# AT42QT1010_Capacitive_Touch_Breakout.net
KiCad netlist of a schematic drawn in EAGLE
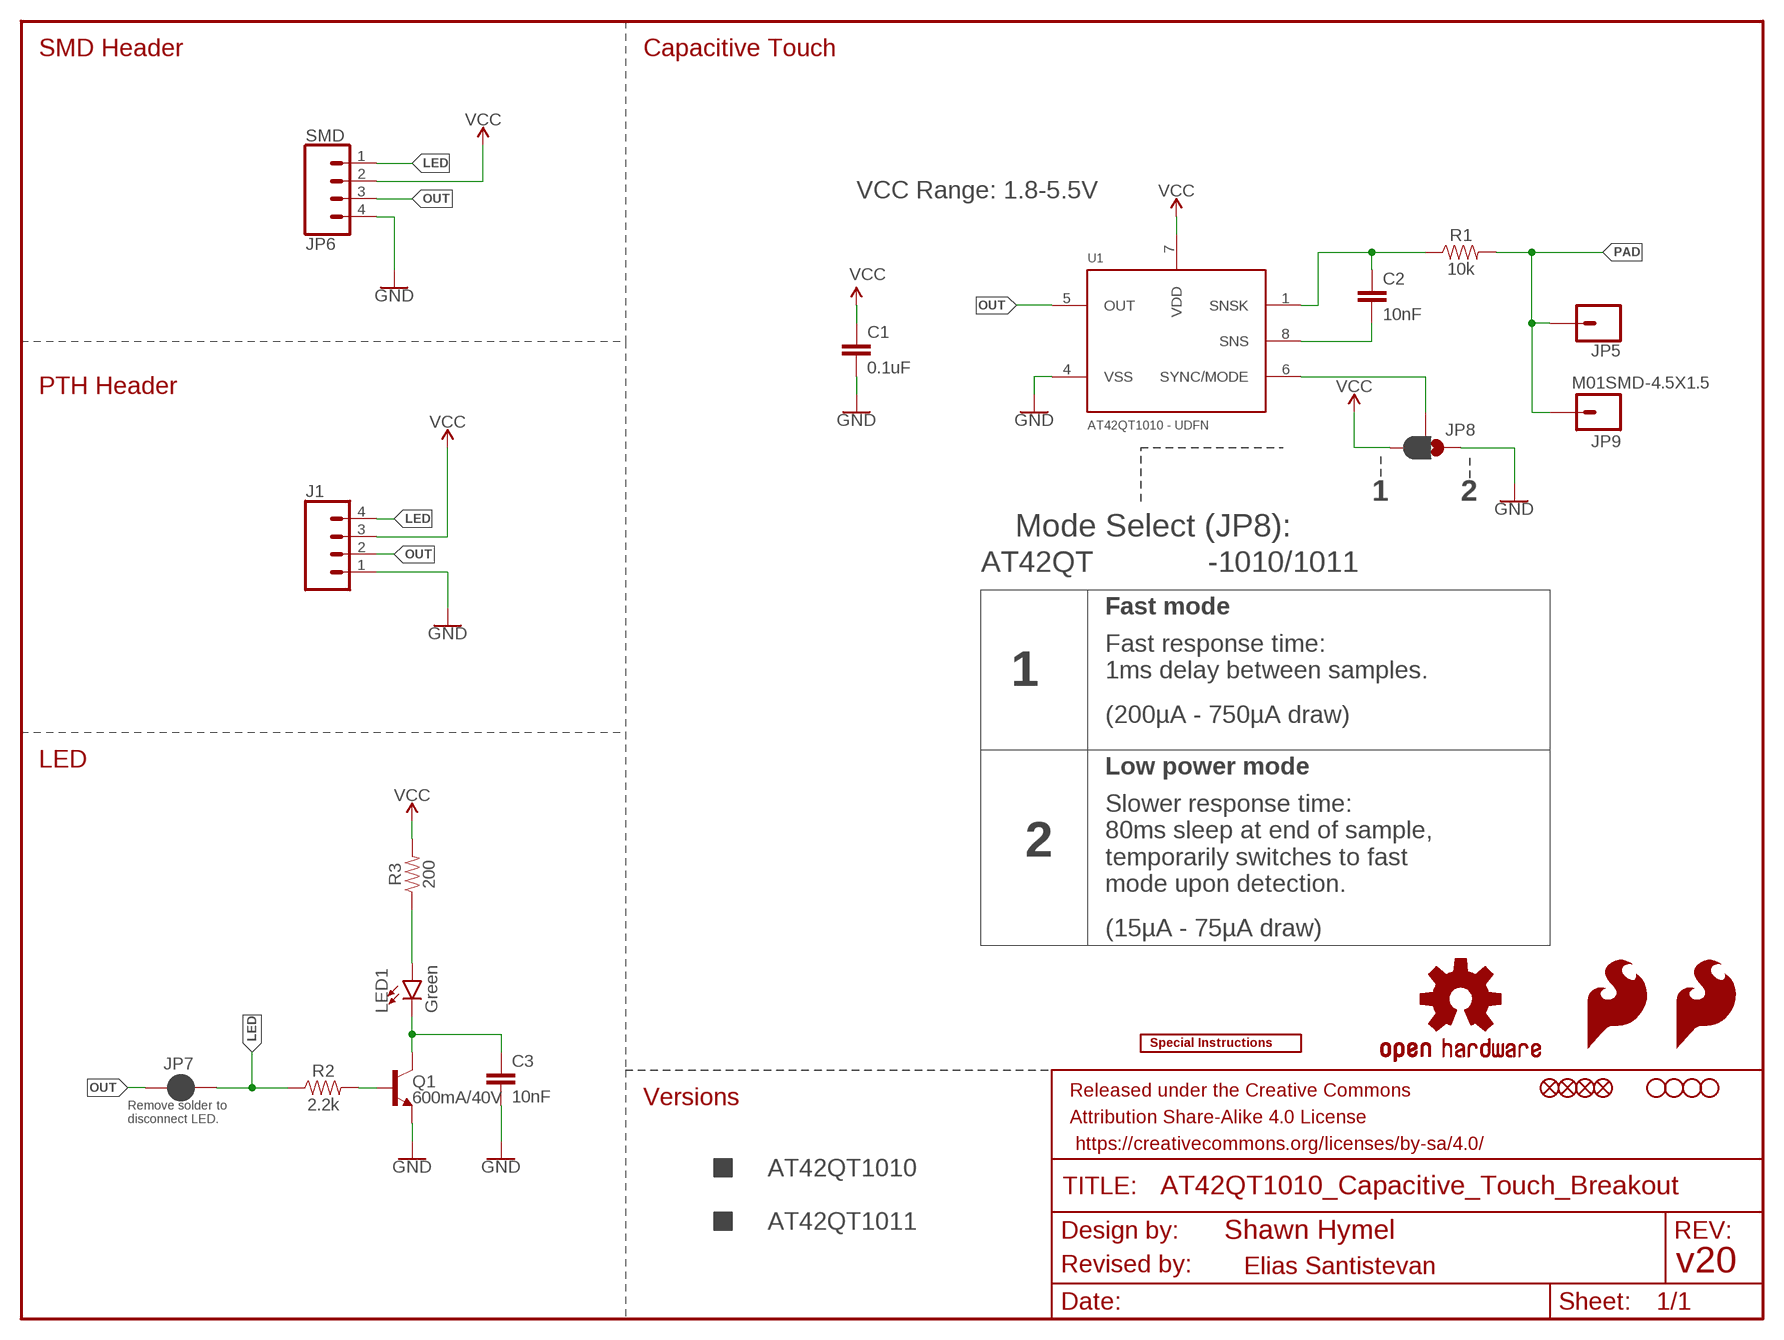
[diagram p0: schematic, sheet 1]

(export (version "E")
  (design (tool "Eeschema 10.0.6"))
  (components
    (comp (ref "C1")
      (value "0.1uF")
      (footprint "eagle-import:0603")
      (libsource (lib "eagle-import") (part "0.1UF-0603-25V-(+80/-20%)"))
    )
    (comp (ref "C2")
      (value "10nF")
      (footprint "eagle-import:0603")
      (libsource (lib "eagle-import") (part "10NF-0603-50V-10%"))
    )
    (comp (ref "C3")
      (value "10nF")
      (footprint "eagle-import:0603")
      (libsource (lib "eagle-import") (part "10NF-0603-50V-10%"))
    )
    (comp (ref "FID1")
      (value "FIDUCIAL1X2")
      (footprint "eagle-import:FIDUCIAL-1X2")
      (libsource (lib "eagle-import") (part "FIDUCIAL1X2"))
    )
    (comp (ref "FID2")
      (value "FIDUCIAL1X2")
      (footprint "eagle-import:FIDUCIAL-1X2")
      (libsource (lib "eagle-import") (part "FIDUCIAL1X2"))
    )
    (comp (ref "FID3")
      (value "FIDUCIAL1X2")
      (footprint "eagle-import:FIDUCIAL-1X2")
      (libsource (lib "eagle-import") (part "FIDUCIAL1X2"))
    )
    (comp (ref "FID4")
      (value "FIDUCIAL1X2")
      (footprint "eagle-import:FIDUCIAL-1X2")
      (libsource (lib "eagle-import") (part "FIDUCIAL1X2"))
    )
    (comp (ref "FRAME1")
      (value "FRAME-LETTER")
      (footprint "eagle-import:CREATIVE_COMMONS")
      (libsource (lib "eagle-import") (part "FRAME-LETTER"))
    )
    (comp (ref "J1")
      (value "CONN_04")
      (footprint "eagle-import:1X04")
      (libsource (lib "eagle-import") (part "CONN_04"))
    )
    (comp (ref "JP5")
      (value "CONN_01")
      (footprint "eagle-import:1X01")
      (libsource (lib "eagle-import") (part "CONN_01"))
    )
    (comp (ref "JP6")
      (value "SMD")
      (footprint "eagle-import:1X04_SMD_RA_MALE")
      (libsource (lib "eagle-import") (part "CONN_04SMD"))
    )
    (comp (ref "JP7")
      (value "JUMPER-SMT_2_NC_PASTE_SILK")
      (footprint "eagle-import:SMT-JUMPER_2_NC_PASTE_SILK")
      (libsource (lib "eagle-import") (part "JUMPER-SMT_2_NC_PASTE_SILK"))
    )
    (comp (ref "JP8")
      (value "JUMPER-SMT_3_1-NC_PASTE_SILK")
      (footprint "eagle-import:SMT-JUMPER_3_1-NC_PASTE_SILK")
      (libsource (lib "eagle-import") (part "JUMPER-SMT_3_1-NC_PASTE_SILK"))
    )
    (comp (ref "JP9")
      (value "M01SMD-4.5X1.5")
      (footprint "eagle-import:PAD-1.5X4.5")
      (libsource (lib "eagle-import") (part "M01SMD-4.5X1.5"))
    )
    (comp (ref "LED1")
      (value "Green")
      (footprint "eagle-import:LED-1206-BOTTOM")
      (libsource (lib "eagle-import") (part "LED-GREEN1206-BOTTOM"))
    )
    (comp (ref "LOGO1")
      (value "SFE_LOGO_FLAME.2_INCH")
      (footprint "eagle-import:SFE_LOGO_FLAME_.2")
      (libsource (lib "eagle-import") (part "SFE_LOGO_FLAME.2_INCH"))
    )
    (comp (ref "LOGO2")
      (value "OSHW-LOGOS")
      (footprint "eagle-import:OSHW-LOGO-S")
      (libsource (lib "eagle-import") (part "OSHW-LOGOS"))
    )
    (comp (ref "LOGO4")
      (value "SFE_LOGO_FLAME.2_INCH")
      (footprint "eagle-import:SFE_LOGO_FLAME_.2")
      (libsource (lib "eagle-import") (part "SFE_LOGO_FLAME.2_INCH"))
    )
    (comp (ref "Q1")
      (value "600mA/40V")
      (footprint "eagle-import:SOT23-3")
      (libsource (lib "eagle-import") (part "TRANS_NPN-MMBT2222AL"))
    )
    (comp (ref "R1")
      (value "10k")
      (footprint "eagle-import:0603")
      (libsource (lib "eagle-import") (part "10KOHM-0603-1/10W-1%"))
    )
    (comp (ref "R2")
      (value "2.2k")
      (footprint "eagle-import:0603")
      (libsource (lib "eagle-import") (part "2.2KOHM-0603-1/10W-1%"))
    )
    (comp (ref "R3")
      (value "200")
      (footprint "eagle-import:0603")
      (libsource (lib "eagle-import") (part "200OHM-0603-1/10W-1%"))
    )
    (comp (ref "STANDOFF1")
      (value "STAND-OFF")
      (footprint "eagle-import:STAND-OFF")
      (libsource (lib "eagle-import") (part "STAND-OFF"))
    )
    (comp (ref "STANDOFF2")
      (value "STAND-OFF")
      (footprint "eagle-import:STAND-OFF")
      (libsource (lib "eagle-import") (part "STAND-OFF"))
    )
    (comp (ref "STANDOFF3")
      (value "STAND-OFF")
      (footprint "eagle-import:STAND-OFF")
      (libsource (lib "eagle-import") (part "STAND-OFF"))
    )
    (comp (ref "STANDOFF4")
      (value "STAND-OFF")
      (footprint "eagle-import:STAND-OFF")
      (libsource (lib "eagle-import") (part "STAND-OFF"))
    )
    (comp (ref "U$1")
      (value "SPECIAL_INSTRUCTIONS-ORDERING")
      (footprint "eagle-import:ORDERING_INSTRUCTIONS")
      (libsource (lib "eagle-import") (part "SPECIAL_INSTRUCTIONS-ORDERING"))
    )
    (comp (ref "U1")
      (value "AT42QT1010 - UDFN")
      (footprint "eagle-import:UDFN_USON_8_PAD")
      (libsource (lib "eagle-import") (part "AT42QT1010UDFN"))
    )
  )
  (nets
    (net (code "1") (name "GND") (class "Default")
      (node (ref "C1") (pin "2") (pinfunction "2_2") (pintype "passive"))
      (node (ref "C3") (pin "2") (pinfunction "2_2") (pintype "passive"))
      (node (ref "J1") (pin "1") (pinfunction "1_1") (pintype "passive"))
      (node (ref "JP6") (pin "4") (pinfunction "4_4") (pintype "passive"))
      (node (ref "JP8") (pin "1") (pinfunction "1_1") (pintype "passive"))
      (node (ref "Q1") (pin "2") (pinfunction "E_2") (pintype "passive"))
      (node (ref "U1") (pin "4") (pinfunction "VSS_4") (pintype "bidirectional"))
    )
    (net (code "2") (name "LED") (class "Default")
      (node (ref "J1") (pin "4") (pinfunction "4_4") (pintype "passive"))
      (node (ref "JP6") (pin "1") (pinfunction "1_1") (pintype "passive"))
      (node (ref "JP7") (pin "2") (pinfunction "2_2") (pintype "passive"))
      (node (ref "R2") (pin "1") (pinfunction "1_1") (pintype "passive"))
    )
    (net (code "3") (name "Net-(LED1-PadA)") (class "Default")
      (node (ref "LED1") (pin "A") (pinfunction "A_A") (pintype "passive"))
      (node (ref "R3") (pin "1") (pinfunction "1_1") (pintype "passive"))
    )
    (net (code "4") (name "Net-(Q1-B)") (class "Default")
      (node (ref "Q1") (pin "1") (pinfunction "B_1") (pintype "passive"))
      (node (ref "R2") (pin "2") (pinfunction "2_2") (pintype "passive"))
    )
    (net (code "5") (name "Net-(Q1-C)") (class "Default")
      (node (ref "C3") (pin "1") (pinfunction "1_1") (pintype "passive"))
      (node (ref "LED1") (pin "C") (pinfunction "C_C") (pintype "passive"))
      (node (ref "Q1") (pin "3") (pinfunction "C_3") (pintype "passive"))
    )
    (net (code "6") (name "Net-(U1-SNS)") (class "Default")
      (node (ref "C2") (pin "2") (pinfunction "2_2") (pintype "passive"))
      (node (ref "U1") (pin "8") (pinfunction "SNS_8") (pintype "bidirectional"))
    )
    (net (code "7") (name "Net-(U1-SNSK)") (class "Default")
      (node (ref "C2") (pin "1") (pinfunction "1_1") (pintype "passive"))
      (node (ref "R1") (pin "1") (pinfunction "1_1") (pintype "passive"))
      (node (ref "U1") (pin "1") (pinfunction "SNSK_1") (pintype "bidirectional"))
    )
    (net (code "8") (name "Net-(U1-SYNC{slash}MODE)") (class "Default")
      (node (ref "JP8") (pin "2") (pinfunction "2_2") (pintype "passive"))
      (node (ref "U1") (pin "6") (pinfunction "SYNC/MODE_6") (pintype "bidirectional"))
    )
    (net (code "9") (name "OUT") (class "Default")
      (node (ref "J1") (pin "2") (pinfunction "2_2") (pintype "passive"))
      (node (ref "JP6") (pin "3") (pinfunction "3_3") (pintype "passive"))
      (node (ref "JP7") (pin "1") (pinfunction "1_1") (pintype "passive"))
      (node (ref "U1") (pin "5") (pinfunction "OUT_5") (pintype "bidirectional"))
    )
    (net (code "10") (name "PAD") (class "Default")
      (node (ref "JP5") (pin "1") (pinfunction "1_1") (pintype "passive"))
      (node (ref "JP9") (pin "P$1") (pinfunction "1_P$1") (pintype "passive"))
      (node (ref "R1") (pin "2") (pinfunction "2_2") (pintype "passive"))
    )
    (net (code "11") (name "VCC") (class "Default")
      (node (ref "C1") (pin "1") (pinfunction "1_1") (pintype "passive"))
      (node (ref "J1") (pin "3") (pinfunction "3_3") (pintype "passive"))
      (node (ref "JP6") (pin "2") (pinfunction "2_2") (pintype "passive"))
      (node (ref "JP8") (pin "3") (pinfunction "3_3") (pintype "passive"))
      (node (ref "R3") (pin "2") (pinfunction "2_2") (pintype "passive"))
      (node (ref "U1") (pin "7") (pinfunction "VDD_7") (pintype "bidirectional"))
    )
  )
)
